# ME433_1.net
KiCad netlist of a schematic drawn in EAGLE
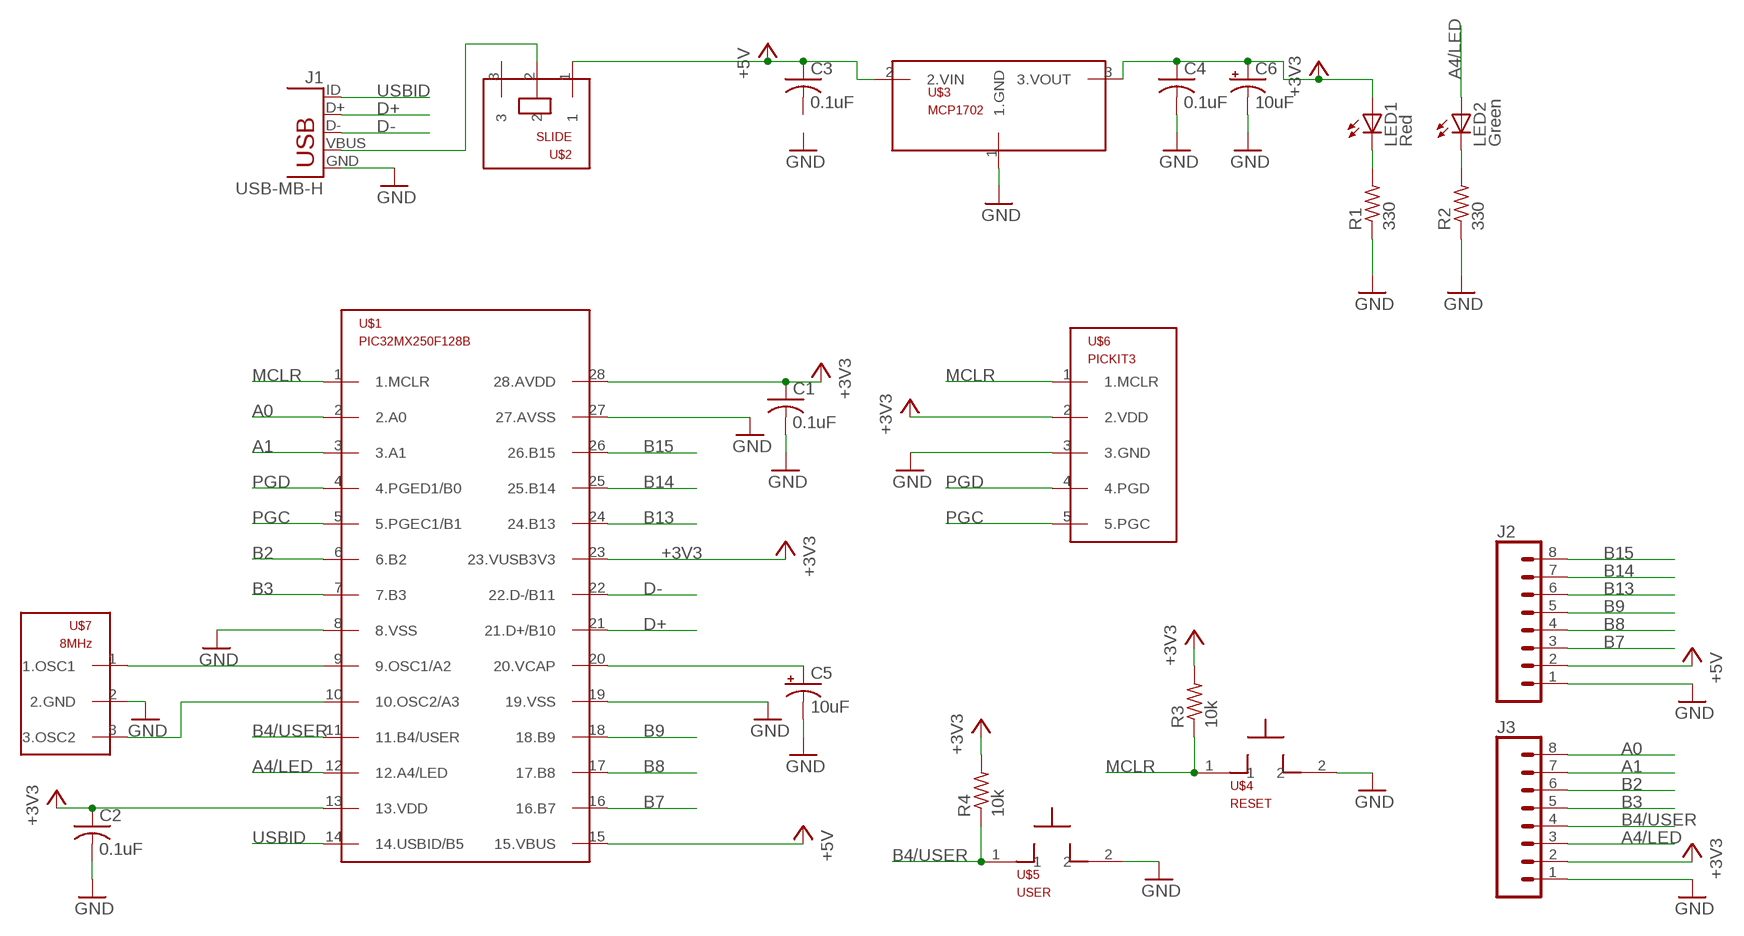
[diagram p0: schematic, sheet 1]

(export (version "E")
  (design (tool "Eeschema 10.0.6"))
  (components
    (comp (ref "C1")
      (value "0.1uF")
      (footprint "eagle-import:C025-025X050")
      (libsource (lib "eagle-import") (part "C-US025-025X050"))
    )
    (comp (ref "C2")
      (value "0.1uF")
      (footprint "eagle-import:C025-025X050")
      (libsource (lib "eagle-import") (part "C-US025-025X050"))
    )
    (comp (ref "C3")
      (value "0.1uF")
      (footprint "eagle-import:C025-025X050")
      (libsource (lib "eagle-import") (part "C-US025-025X050"))
    )
    (comp (ref "C4")
      (value "0.1uF")
      (footprint "eagle-import:C025-025X050")
      (libsource (lib "eagle-import") (part "C-US025-025X050"))
    )
    (comp (ref "C5")
      (value "10uF")
      (footprint "eagle-import:B45181B")
      (libsource (lib "eagle-import") (part "CPOL-USB45181B"))
    )
    (comp (ref "C6")
      (value "10uF")
      (footprint "eagle-import:B45181B")
      (libsource (lib "eagle-import") (part "CPOL-USB45181B"))
    )
    (comp (ref "J1")
      (value "USB-MB-H")
      (footprint "eagle-import:USB-MB-H")
      (libsource (lib "eagle-import") (part "USB-MB-H"))
    )
    (comp (ref "J2")
      (value "CONN_08\"")
      (footprint "eagle-import:1X08")
      (libsource (lib "eagle-import") (part "CONN_08{dblquote}"))
    )
    (comp (ref "J3")
      (value "CONN_08\"")
      (footprint "eagle-import:1X08")
      (libsource (lib "eagle-import") (part "CONN_08{dblquote}"))
    )
    (comp (ref "LED1")
      (value "Red")
      (footprint "eagle-import:LED3MM")
      (libsource (lib "eagle-import") (part "LED3MM"))
    )
    (comp (ref "LED2")
      (value "Green")
      (footprint "eagle-import:LED3MM")
      (libsource (lib "eagle-import") (part "LED3MM"))
    )
    (comp (ref "R1")
      (value "330")
      (footprint "eagle-import:0207_10")
      (libsource (lib "eagle-import") (part "R-US_0207/10"))
    )
    (comp (ref "R2")
      (value "330")
      (footprint "eagle-import:0207_10")
      (libsource (lib "eagle-import") (part "R-US_0207/10"))
    )
    (comp (ref "R3")
      (value "10k")
      (footprint "eagle-import:0207_10")
      (libsource (lib "eagle-import") (part "R-US_0207/10"))
    )
    (comp (ref "R4")
      (value "10k")
      (footprint "eagle-import:0207_10")
      (libsource (lib "eagle-import") (part "R-US_0207/10"))
    )
    (comp (ref "U$1")
      (value "PIC32MX250F128B")
      (footprint "eagle-import:DIL28-3")
      (libsource (lib "eagle-import") (part "PIC32MX250F128B"))
    )
    (comp (ref "U$2")
      (value "SLIDE")
      (footprint "eagle-import:SLIDE")
      (libsource (lib "eagle-import") (part "SLIDE"))
    )
    (comp (ref "U$3")
      (value "MCP1702")
      (footprint "eagle-import:TO92")
      (libsource (lib "eagle-import") (part "MCP1702"))
    )
    (comp (ref "U$4")
      (value "RESET")
      (footprint "eagle-import:PB")
      (libsource (lib "eagle-import") (part "PB"))
    )
    (comp (ref "U$5")
      (value "USER")
      (footprint "eagle-import:PB")
      (libsource (lib "eagle-import") (part "PB"))
    )
    (comp (ref "U$6")
      (value "PICKIT3")
      (footprint "eagle-import:1X05")
      (libsource (lib "eagle-import") (part "PICKIT3"))
    )
    (comp (ref "U$7")
      (value "8MHz")
      (footprint "eagle-import:OSC")
      (libsource (lib "eagle-import") (part "OSC"))
    )
  )
  (nets
    (net (code "1") (name "+3V3") (class "Default")
      (node (ref "C1") (pin "1") (pinfunction "1_1") (pintype "passive"))
      (node (ref "C2") (pin "1") (pinfunction "1_1") (pintype "passive"))
      (node (ref "C4") (pin "1") (pinfunction "1_1") (pintype "passive"))
      (node (ref "C6") (pin "+") (pinfunction "+_+") (pintype "passive"))
      (node (ref "J3") (pin "2") (pinfunction "2_2") (pintype "passive"))
      (node (ref "LED1") (pin "A") (pinfunction "A_A") (pintype "passive"))
      (node (ref "R3") (pin "2") (pinfunction "2_2") (pintype "passive"))
      (node (ref "R4") (pin "2") (pinfunction "2_2") (pintype "passive"))
      (node (ref "U$1") (pin "13") (pinfunction "13.VDD_13") (pintype "bidirectional"))
      (node (ref "U$1") (pin "23") (pinfunction "23.VUSB3V3_23") (pintype "bidirectional"))
      (node (ref "U$1") (pin "28") (pinfunction "28.AVDD_28") (pintype "bidirectional"))
      (node (ref "U$3") (pin "3") (pinfunction "3.VOUT_3") (pintype "bidirectional"))
      (node (ref "U$6") (pin "2") (pinfunction "2.VDD_2") (pintype "bidirectional"))
    )
    (net (code "2") (name "+5V") (class "Default")
      (node (ref "C3") (pin "1") (pinfunction "1_1") (pintype "passive"))
      (node (ref "J2") (pin "2") (pinfunction "2_2") (pintype "passive"))
      (node (ref "U$1") (pin "15") (pinfunction "15.VBUS_15") (pintype "bidirectional"))
      (node (ref "U$2") (pin "1") (pinfunction "1_1") (pintype "bidirectional"))
      (node (ref "U$3") (pin "2") (pinfunction "2.VIN_2") (pintype "bidirectional"))
    )
    (net (code "3") (name "/A0") (class "Default")
      (node (ref "J3") (pin "8") (pinfunction "8_8") (pintype "passive"))
      (node (ref "U$1") (pin "2") (pinfunction "2.A0_2") (pintype "bidirectional"))
    )
    (net (code "4") (name "/A1") (class "Default")
      (node (ref "J3") (pin "7") (pinfunction "7_7") (pintype "passive"))
      (node (ref "U$1") (pin "3") (pinfunction "3.A1_3") (pintype "bidirectional"))
    )
    (net (code "5") (name "/A4{slash}LED") (class "Default")
      (node (ref "J3") (pin "3") (pinfunction "3_3") (pintype "passive"))
      (node (ref "LED2") (pin "A") (pinfunction "A_A") (pintype "passive"))
      (node (ref "U$1") (pin "12") (pinfunction "12.A4/LED_12") (pintype "bidirectional"))
    )
    (net (code "6") (name "/B2") (class "Default")
      (node (ref "J3") (pin "6") (pinfunction "6_6") (pintype "passive"))
      (node (ref "U$1") (pin "6") (pinfunction "6.B2_6") (pintype "bidirectional"))
    )
    (net (code "7") (name "/B3") (class "Default")
      (node (ref "J3") (pin "5") (pinfunction "5_5") (pintype "passive"))
      (node (ref "U$1") (pin "7") (pinfunction "7.B3_7") (pintype "bidirectional"))
    )
    (net (code "8") (name "/B4{slash}USER") (class "Default")
      (node (ref "J3") (pin "4") (pinfunction "4_4") (pintype "passive"))
      (node (ref "R4") (pin "1") (pinfunction "1_1") (pintype "passive"))
      (node (ref "U$1") (pin "11") (pinfunction "11.B4/USER_11") (pintype "bidirectional"))
      (node (ref "U$5") (pin "1") (pinfunction "1_1") (pintype "bidirectional"))
    )
    (net (code "9") (name "/B7") (class "Default")
      (node (ref "J2") (pin "3") (pinfunction "3_3") (pintype "passive"))
      (node (ref "U$1") (pin "16") (pinfunction "16.B7_16") (pintype "bidirectional"))
    )
    (net (code "10") (name "/B8") (class "Default")
      (node (ref "J2") (pin "4") (pinfunction "4_4") (pintype "passive"))
      (node (ref "U$1") (pin "17") (pinfunction "17.B8_17") (pintype "bidirectional"))
    )
    (net (code "11") (name "/B9") (class "Default")
      (node (ref "J2") (pin "5") (pinfunction "5_5") (pintype "passive"))
      (node (ref "U$1") (pin "18") (pinfunction "18.B9_18") (pintype "bidirectional"))
    )
    (net (code "12") (name "/B13") (class "Default")
      (node (ref "J2") (pin "6") (pinfunction "6_6") (pintype "passive"))
      (node (ref "U$1") (pin "24") (pinfunction "24.B13_24") (pintype "bidirectional"))
    )
    (net (code "13") (name "/B14") (class "Default")
      (node (ref "J2") (pin "7") (pinfunction "7_7") (pintype "passive"))
      (node (ref "U$1") (pin "25") (pinfunction "25.B14_25") (pintype "bidirectional"))
    )
    (net (code "14") (name "/B15") (class "Default")
      (node (ref "J2") (pin "8") (pinfunction "8_8") (pintype "passive"))
      (node (ref "U$1") (pin "26") (pinfunction "26.B15_26") (pintype "bidirectional"))
    )
    (net (code "15") (name "/D+") (class "Default")
      (node (ref "J1") (pin "D+") (pinfunction "D+_D+") (pintype "bidirectional"))
      (node (ref "U$1") (pin "21") (pinfunction "21.D+/B10_21") (pintype "bidirectional"))
    )
    (net (code "16") (name "/D-") (class "Default")
      (node (ref "J1") (pin "D-") (pinfunction "D-_D-") (pintype "bidirectional"))
      (node (ref "U$1") (pin "22") (pinfunction "22.D-/B11_22") (pintype "bidirectional"))
    )
    (net (code "17") (name "/MCLR") (class "Default")
      (node (ref "R3") (pin "1") (pinfunction "1_1") (pintype "passive"))
      (node (ref "U$1") (pin "1") (pinfunction "1.MCLR_1") (pintype "bidirectional"))
      (node (ref "U$4") (pin "1") (pinfunction "1_1") (pintype "bidirectional"))
      (node (ref "U$6") (pin "1") (pinfunction "1.MCLR_1") (pintype "bidirectional"))
    )
    (net (code "18") (name "/PGC") (class "Default")
      (node (ref "U$1") (pin "5") (pinfunction "5.PGEC1/B1_5") (pintype "bidirectional"))
      (node (ref "U$6") (pin "5") (pinfunction "5.PGC_5") (pintype "bidirectional"))
    )
    (net (code "19") (name "/PGD") (class "Default")
      (node (ref "U$1") (pin "4") (pinfunction "4.PGED1/B0_4") (pintype "bidirectional"))
      (node (ref "U$6") (pin "4") (pinfunction "4.PGD_4") (pintype "bidirectional"))
    )
    (net (code "20") (name "/USBID") (class "Default")
      (node (ref "J1") (pin "ID") (pinfunction "ID_ID") (pintype "bidirectional"))
      (node (ref "U$1") (pin "14") (pinfunction "14.USBID/B5_14") (pintype "bidirectional"))
    )
    (net (code "21") (name "GND") (class "Default")
      (node (ref "C1") (pin "2") (pinfunction "2_2") (pintype "passive"))
      (node (ref "C2") (pin "2") (pinfunction "2_2") (pintype "passive"))
      (node (ref "C4") (pin "2") (pinfunction "2_2") (pintype "passive"))
      (node (ref "C5") (pin "-") (pinfunction "-_-") (pintype "passive"))
      (node (ref "C6") (pin "-") (pinfunction "-_-") (pintype "passive"))
      (node (ref "J1") (pin "GND") (pinfunction "GND_GND") (pintype "bidirectional"))
      (node (ref "J2") (pin "1") (pinfunction "1_1") (pintype "passive"))
      (node (ref "J3") (pin "1") (pinfunction "1_1") (pintype "passive"))
      (node (ref "R1") (pin "1") (pinfunction "1_1") (pintype "passive"))
      (node (ref "R2") (pin "1") (pinfunction "1_1") (pintype "passive"))
      (node (ref "U$1") (pin "19") (pinfunction "19.VSS_19") (pintype "bidirectional"))
      (node (ref "U$1") (pin "27") (pinfunction "27.AVSS_27") (pintype "bidirectional"))
      (node (ref "U$1") (pin "8") (pinfunction "8.VSS_8") (pintype "bidirectional"))
      (node (ref "U$3") (pin "1") (pinfunction "1.GND_1") (pintype "bidirectional"))
      (node (ref "U$4") (pin "2") (pinfunction "2_2") (pintype "bidirectional"))
      (node (ref "U$5") (pin "2") (pinfunction "2_2") (pintype "bidirectional"))
      (node (ref "U$6") (pin "3") (pinfunction "3.GND_3") (pintype "bidirectional"))
      (node (ref "U$7") (pin "2") (pinfunction "2.GND_2") (pintype "bidirectional"))
    )
    (net (code "22") (name "Net-(J1-PadVBUS)") (class "Default")
      (node (ref "J1") (pin "VBUS") (pinfunction "VBUS_VBUS") (pintype "bidirectional"))
      (node (ref "U$2") (pin "2") (pinfunction "2_2") (pintype "bidirectional"))
    )
    (net (code "23") (name "Net-(LED1-C)") (class "Default")
      (node (ref "LED1") (pin "K") (pinfunction "C_K") (pintype "passive"))
      (node (ref "R1") (pin "2") (pinfunction "2_2") (pintype "passive"))
    )
    (net (code "24") (name "Net-(LED2-C)") (class "Default")
      (node (ref "LED2") (pin "K") (pinfunction "C_K") (pintype "passive"))
      (node (ref "R2") (pin "2") (pinfunction "2_2") (pintype "passive"))
    )
    (net (code "25") (name "Net-(U$1-9.OSC1{slash}A2)") (class "Default")
      (node (ref "U$1") (pin "9") (pinfunction "9.OSC1/A2_9") (pintype "bidirectional"))
      (node (ref "U$7") (pin "1") (pinfunction "1.OSC1_1") (pintype "bidirectional"))
    )
    (net (code "26") (name "Net-(U$1-10.OSC2{slash}A3)") (class "Default")
      (node (ref "U$1") (pin "10") (pinfunction "10.OSC2/A3_10") (pintype "bidirectional"))
      (node (ref "U$7") (pin "3") (pinfunction "3.OSC2_3") (pintype "bidirectional"))
    )
    (net (code "27") (name "Net-(U$1-20.VCAP)") (class "Default")
      (node (ref "C5") (pin "+") (pinfunction "+_+") (pintype "passive"))
      (node (ref "U$1") (pin "20") (pinfunction "20.VCAP_20") (pintype "bidirectional"))
    )
    (net (code "28") (name "unconnected-(C3-Pad2)") (class "Default")
      (node (ref "C3") (pin "2") (pinfunction "2_2") (pintype "passive"))
    )
    (net (code "29") (name "unconnected-(U$2-Pad3)") (class "Default")
      (node (ref "U$2") (pin "3") (pinfunction "3_3") (pintype "bidirectional"))
    )
  )
)
